# Diana.net
KiCad netlist of a schematic drawn in Altium Designer
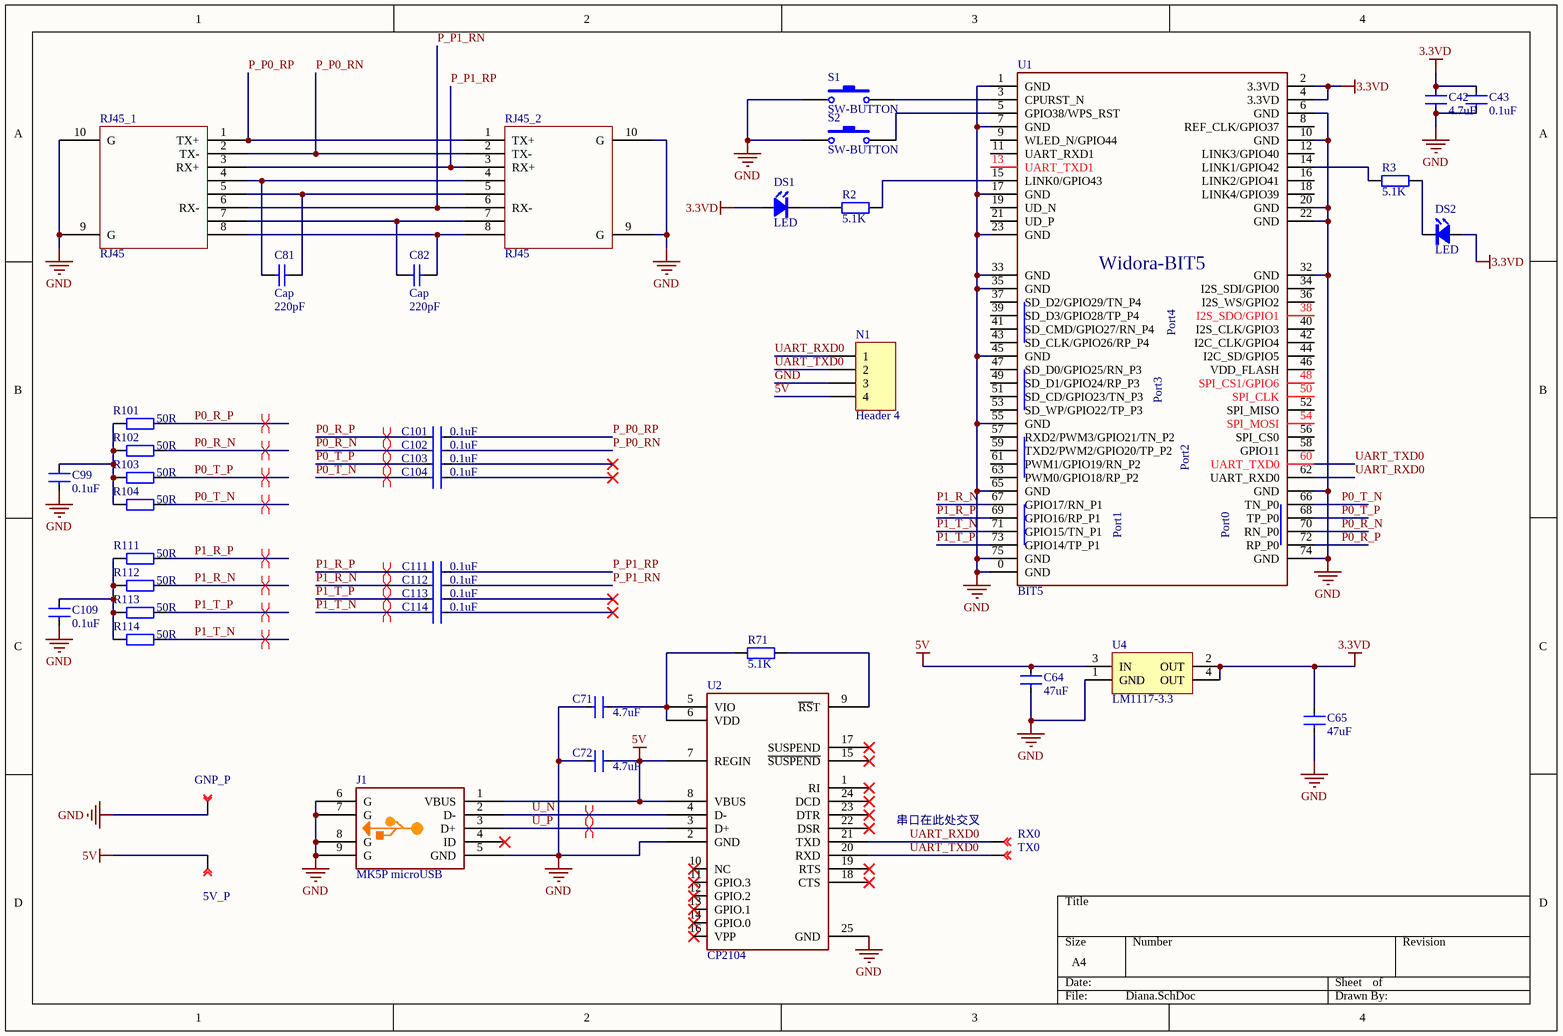
[diagram p0: Diana.SchDoc]

(export (version "E")
  (design (tool "Eeschema 10.0.6"))
  (components
    (comp (ref "5V_P")
      (value "TEST POINT")
      (footprint "TEST-POINT")
      (description "Description")
      (libsource (lib "KIT") (part "TP"))
    )
    (comp (ref "C42")
      (value "4.7uF")
      (footprint "C0402")
      (description "普通小电容")
      (libsource (lib "KIT") (part "CAP"))
    )
    (comp (ref "C43")
      (value "0.1uF")
      (footprint "C0402")
      (description "普通小电容")
      (libsource (lib "KIT") (part "CAP"))
    )
    (comp (ref "C64")
      (value "47uF")
      (footprint "0805C")
      (description "普通小电容")
      (libsource (lib "KIT") (part "CAP"))
    )
    (comp (ref "C65")
      (value "47uF")
      (footprint "0805C")
      (description "普通小电容")
      (libsource (lib "KIT") (part "CAP"))
    )
    (comp (ref "C71")
      (value "4.7uF")
      (footprint "C0402")
      (description "普通小电容")
      (libsource (lib "KIT") (part "CAP"))
    )
    (comp (ref "C72")
      (value "4.7uF")
      (footprint "C0402")
      (description "普通小电容")
      (libsource (lib "KIT") (part "CAP"))
    )
    (comp (ref "C81")
      (value "Cap")
      (footprint "C0402")
      (description "Capacitor")
      (fields (field (name "ALTIUM_VALUE") "220pF") (field (name "PUBLISHER") "Altium Limited"))
      (libsource (lib "Miscellaneous Devices") (part "Cap"))
    )
    (comp (ref "C82")
      (value "Cap")
      (footprint "C0402")
      (description "Capacitor")
      (fields (field (name "ALTIUM_VALUE") "220pF") (field (name "PUBLISHER") "Altium Limited"))
      (libsource (lib "Miscellaneous Devices") (part "Cap"))
    )
    (comp (ref "C99")
      (value "0.1uF")
      (footprint "C0402")
      (description "普通小电容")
      (libsource (lib "KIT") (part "CAP"))
    )
    (comp (ref "C101")
      (value "0.1uF")
      (footprint "C0402")
      (description "普通小电容")
      (libsource (lib "KIT") (part "CAP"))
    )
    (comp (ref "C102")
      (value "0.1uF")
      (footprint "C0402")
      (description "普通小电容")
      (libsource (lib "KIT") (part "CAP"))
    )
    (comp (ref "C103")
      (value "0.1uF")
      (footprint "C0402")
      (description "普通小电容")
      (libsource (lib "KIT") (part "CAP"))
    )
    (comp (ref "C104")
      (value "0.1uF")
      (footprint "C0402")
      (description "普通小电容")
      (libsource (lib "KIT") (part "CAP"))
    )
    (comp (ref "C109")
      (value "0.1uF")
      (footprint "C0402")
      (description "普通小电容")
      (libsource (lib "KIT") (part "CAP"))
    )
    (comp (ref "C111")
      (value "0.1uF")
      (footprint "C0402")
      (description "普通小电容")
      (libsource (lib "KIT") (part "CAP"))
    )
    (comp (ref "C112")
      (value "0.1uF")
      (footprint "C0402")
      (description "普通小电容")
      (libsource (lib "KIT") (part "CAP"))
    )
    (comp (ref "C113")
      (value "0.1uF")
      (footprint "C0402")
      (description "普通小电容")
      (libsource (lib "KIT") (part "CAP"))
    )
    (comp (ref "C114")
      (value "0.1uF")
      (footprint "C0402")
      (description "普通小电容")
      (libsource (lib "KIT") (part "CAP"))
    )
    (comp (ref "DS1")
      (value "LED")
      (footprint "LED0603")
      (description "RED")
      (libsource (lib "KIT") (part "LED"))
    )
    (comp (ref "DS2")
      (value "LED")
      (footprint "LED0603")
      (description "RED")
      (libsource (lib "") (part "LED_1"))
    )
    (comp (ref "GNP_P")
      (value "TEST POINT")
      (footprint "TEST-POINT")
      (description "Description")
      (libsource (lib "KIT") (part "TP"))
    )
    (comp (ref "J1")
      (value "MK5P microUSB")
      (footprint "MICROUSB")
      (description "4固定脚microUSB座")
      (libsource (lib "KIT") (part "MICRO_USB"))
    )
    (comp (ref "N1")
      (value "Header 4")
      (footprint "HDR-1X4")
      (description "Header, 4-Pin")
      (fields (field (name "PUBLISHER") "Altium Limited"))
      (libsource (lib "Miscellaneous Connectors") (part "Header 4"))
    )
    (comp (ref "R2")
      (value "5.1K")
      (footprint "R0402")
      (description "普通电阻")
      (libsource (lib "KIT") (part "RES"))
    )
    (comp (ref "R3")
      (value "5.1K")
      (footprint "R0402")
      (description "普通电阻")
      (libsource (lib "KIT") (part "RES"))
    )
    (comp (ref "R71")
      (value "5.1K")
      (footprint "R0402")
      (description "普通电阻")
      (libsource (lib "KIT") (part "RES"))
    )
    (comp (ref "R101")
      (value "50R")
      (footprint "R0402")
      (description "普通电阻")
      (libsource (lib "KIT") (part "RES"))
    )
    (comp (ref "R102")
      (value "50R")
      (footprint "R0402")
      (description "普通电阻")
      (libsource (lib "KIT") (part "RES"))
    )
    (comp (ref "R103")
      (value "50R")
      (footprint "R0402")
      (description "普通电阻")
      (libsource (lib "KIT") (part "RES"))
    )
    (comp (ref "R104")
      (value "50R")
      (footprint "R0402")
      (description "普通电阻")
      (libsource (lib "KIT") (part "RES"))
    )
    (comp (ref "R111")
      (value "50R")
      (footprint "R0402")
      (description "普通电阻")
      (libsource (lib "KIT") (part "RES"))
    )
    (comp (ref "R112")
      (value "50R")
      (footprint "R0402")
      (description "普通电阻")
      (libsource (lib "KIT") (part "RES"))
    )
    (comp (ref "R113")
      (value "50R")
      (footprint "R0402")
      (description "普通电阻")
      (libsource (lib "KIT") (part "RES"))
    )
    (comp (ref "R114")
      (value "50R")
      (footprint "R0402")
      (description "普通电阻")
      (libsource (lib "KIT") (part "RES"))
    )
    (comp (ref "RJ45_1")
      (value "RJ45")
      (footprint "RJ45")
      (description "RJ45不带网络变压器")
      (libsource (lib "KIT") (part "RJ45"))
    )
    (comp (ref "RJ45_2")
      (value "RJ45")
      (footprint "RJ45")
      (description "RJ45不带网络变压器")
      (libsource (lib "") (part "RJ45_1"))
    )
    (comp (ref "RX0")
      (value "TEST POINT")
      (footprint "TEST-POINT")
      (description "Description")
      (libsource (lib "KIT") (part "TP"))
    )
    (comp (ref "S1") (value "SW-BUTTON") (footprint "MINIBUTTON") (libsource (lib "KIT") (part "SW-BUTTON")))
    (comp (ref "S2") (value "SW-BUTTON") (footprint "MINIBUTTON") (libsource (lib "KIT") (part "SW-BUTTON")))
    (comp (ref "TX0")
      (value "TEST POINT")
      (footprint "TEST-POINT")
      (description "Description")
      (libsource (lib "KIT") (part "TP"))
    )
    (comp (ref "U1")
      (value "BIT5")
      (footprint "NGFF_M_2-EKEY")
      (description "NGFF M.2 E KEY")
      (libsource (lib "BIT345") (part "BIT5"))
    )
    (comp (ref "U2") (value "CP2104") (footprint "QFN24") (libsource (lib "KIT") (part "CP2104")))
    (comp (ref "U4")
      (value "LM1117-3.3")
      (footprint "SOT223-4N")
      (description "800mA and 1A Low Dropout Positive Regulator 2.85V, 3.3V, 5V, and Adjustable")
      (fields (field (name "PUBLISHER") "Altium Limited"))
      (libsource (lib "KIT") (part "LM1117-3.3"))
    )
  )
  (nets
    (net (code "1") (name "/P0_R_N") (class "Default")
      (node (ref "C102") (pin "1") (pinfunction "1_1") (pintype "passive"))
      (node (ref "R102") (pin "2") (pinfunction "2_2") (pintype "passive"))
      (node (ref "U1") (pin "70") (pinfunction "RN_P0_70") (pintype "passive"))
    )
    (net (code "2") (name "/P0_R_P") (class "Default")
      (node (ref "C101") (pin "1") (pinfunction "1_1") (pintype "passive"))
      (node (ref "R101") (pin "2") (pinfunction "2_2") (pintype "passive"))
      (node (ref "U1") (pin "72") (pinfunction "RP_P0_72") (pintype "passive"))
    )
    (net (code "3") (name "/P0_T_N") (class "Default")
      (node (ref "C104") (pin "1") (pinfunction "1_1") (pintype "passive"))
      (node (ref "R104") (pin "2") (pinfunction "2_2") (pintype "passive"))
      (node (ref "U1") (pin "66") (pinfunction "TN_P0_66") (pintype "passive"))
    )
    (net (code "4") (name "/P0_T_P") (class "Default")
      (node (ref "C103") (pin "1") (pinfunction "1_1") (pintype "passive"))
      (node (ref "R103") (pin "2") (pinfunction "2_2") (pintype "passive"))
      (node (ref "U1") (pin "68") (pinfunction "TP_P0_68") (pintype "passive"))
    )
    (net (code "5") (name "/P1_R_N") (class "Default")
      (node (ref "C112") (pin "1") (pinfunction "1_1") (pintype "passive"))
      (node (ref "R112") (pin "2") (pinfunction "2_2") (pintype "passive"))
      (node (ref "U1") (pin "67") (pinfunction "GPIO17/RN_P1_67") (pintype "passive"))
    )
    (net (code "6") (name "/P1_R_P") (class "Default")
      (node (ref "C111") (pin "1") (pinfunction "1_1") (pintype "passive"))
      (node (ref "R111") (pin "2") (pinfunction "2_2") (pintype "passive"))
      (node (ref "U1") (pin "69") (pinfunction "GPIO16/RP_P1_69") (pintype "passive"))
    )
    (net (code "7") (name "/P1_T_N") (class "Default")
      (node (ref "C114") (pin "1") (pinfunction "1_1") (pintype "passive"))
      (node (ref "R114") (pin "2") (pinfunction "2_2") (pintype "passive"))
      (node (ref "U1") (pin "71") (pinfunction "GPIO15/TN_P1_71") (pintype "passive"))
    )
    (net (code "8") (name "/P1_T_P") (class "Default")
      (node (ref "C113") (pin "1") (pinfunction "1_1") (pintype "passive"))
      (node (ref "R113") (pin "2") (pinfunction "2_2") (pintype "passive"))
      (node (ref "U1") (pin "73") (pinfunction "GPIO14/TP_P1_73") (pintype "passive"))
    )
    (net (code "9") (name "/P_P0_RN") (class "Default")
      (node (ref "C102") (pin "2") (pinfunction "2_2") (pintype "passive"))
      (node (ref "RJ45_1") (pin "2") (pinfunction "TX-_2") (pintype "power_in"))
      (node (ref "RJ45_2") (pin "2") (pinfunction "TX-_2") (pintype "power_in"))
    )
    (net (code "10") (name "/P_P0_RP") (class "Default")
      (node (ref "C101") (pin "2") (pinfunction "2_2") (pintype "passive"))
      (node (ref "RJ45_1") (pin "1") (pinfunction "TX+_1") (pintype "power_in"))
      (node (ref "RJ45_2") (pin "1") (pinfunction "TX+_1") (pintype "power_in"))
    )
    (net (code "11") (name "/P_P1_RN") (class "Default")
      (node (ref "C112") (pin "2") (pinfunction "2_2") (pintype "passive"))
      (node (ref "RJ45_1") (pin "6") (pinfunction "RX-_6") (pintype "power_in"))
      (node (ref "RJ45_2") (pin "6") (pinfunction "RX-_6") (pintype "power_in"))
    )
    (net (code "12") (name "/P_P1_RP") (class "Default")
      (node (ref "C111") (pin "2") (pinfunction "2_2") (pintype "passive"))
      (node (ref "RJ45_1") (pin "3") (pinfunction "RX+_3") (pintype "power_in"))
      (node (ref "RJ45_2") (pin "3") (pinfunction "RX+_3") (pintype "power_in"))
    )
    (net (code "13") (name "/UART_RXD0") (class "Default")
      (node (ref "N1") (pin "1") (pinfunction "1_1") (pintype "passive"))
      (node (ref "RX0") (pin "1") (pinfunction "1_1") (pintype "passive"))
      (node (ref "U1") (pin "62") (pinfunction "UART_RXD0_62") (pintype "passive"))
      (node (ref "U2") (pin "21") (pinfunction "TXD_21") (pintype "passive"))
    )
    (net (code "14") (name "/UART_TXD0") (class "Default")
      (node (ref "N1") (pin "2") (pinfunction "2_2") (pintype "passive"))
      (node (ref "TX0") (pin "1") (pinfunction "1_1") (pintype "passive"))
      (node (ref "U1") (pin "60") (pinfunction "UART_TXD0_60") (pintype "passive"))
      (node (ref "U2") (pin "20") (pinfunction "RXD_20") (pintype "passive"))
    )
    (net (code "15") (name "/U_N") (class "Default")
      (node (ref "J1") (pin "2") (pinfunction "D-_2") (pintype "passive"))
      (node (ref "U2") (pin "4") (pinfunction "D-_4") (pintype "passive"))
    )
    (net (code "16") (name "/U_P") (class "Default")
      (node (ref "J1") (pin "3") (pinfunction "D+_3") (pintype "passive"))
      (node (ref "U2") (pin "3") (pinfunction "D+_3") (pintype "passive"))
    )
    (net (code "17") (name "3.3VD") (class "Default")
      (node (ref "C42") (pin "1") (pinfunction "1_1") (pintype "passive"))
      (node (ref "C43") (pin "1") (pinfunction "1_1") (pintype "passive"))
      (node (ref "C65") (pin "2") (pinfunction "2_2") (pintype "passive"))
      (node (ref "DS1") (pin "A") (pinfunction "1_A") (pintype "passive"))
      (node (ref "DS2") (pin "A") (pinfunction "1_A") (pintype "passive"))
      (node (ref "U1") (pin "2") (pinfunction "3.3VD_2") (pintype "passive"))
      (node (ref "U1") (pin "4") (pinfunction "3.3VD_4") (pintype "passive"))
      (node (ref "U4") (pin "2") (pinfunction "OUT_2") (pintype "power_in"))
      (node (ref "U4") (pin "4") (pinfunction "OUT_4") (pintype "power_in"))
    )
    (net (code "18") (name "5V") (class "Default")
      (node (ref "5V_P") (pin "1") (pinfunction "1_1") (pintype "passive"))
      (node (ref "C64") (pin "1") (pinfunction "1_1") (pintype "passive"))
      (node (ref "C72") (pin "2") (pinfunction "2_2") (pintype "passive"))
      (node (ref "J1") (pin "1") (pinfunction "VBUS_1") (pintype "power_in"))
      (node (ref "N1") (pin "4") (pinfunction "4_4") (pintype "passive"))
      (node (ref "U2") (pin "7") (pinfunction "REGIN_7") (pintype "passive"))
      (node (ref "U2") (pin "8") (pinfunction "VBUS_8") (pintype "power_in"))
      (node (ref "U4") (pin "3") (pinfunction "IN_3") (pintype "power_in"))
    )
    (net (code "19") (name "GND") (class "Default")
      (node (ref "C109") (pin "2") (pinfunction "2_2") (pintype "passive"))
      (node (ref "C42") (pin "2") (pinfunction "2_2") (pintype "passive"))
      (node (ref "C43") (pin "2") (pinfunction "2_2") (pintype "passive"))
      (node (ref "C64") (pin "2") (pinfunction "2_2") (pintype "passive"))
      (node (ref "C65") (pin "1") (pinfunction "1_1") (pintype "passive"))
      (node (ref "C71") (pin "2") (pinfunction "2_2") (pintype "passive"))
      (node (ref "C72") (pin "1") (pinfunction "1_1") (pintype "passive"))
      (node (ref "C99") (pin "2") (pinfunction "2_2") (pintype "passive"))
      (node (ref "GNP_P") (pin "1") (pinfunction "1_1") (pintype "passive"))
      (node (ref "J1") (pin "5") (pinfunction "GND_5") (pintype "power_in"))
      (node (ref "J1") (pin "6") (pinfunction "G_6") (pintype "passive"))
      (node (ref "J1") (pin "7") (pinfunction "G_7") (pintype "passive"))
      (node (ref "J1") (pin "8") (pinfunction "G_8") (pintype "passive"))
      (node (ref "J1") (pin "9") (pinfunction "G_9") (pintype "passive"))
      (node (ref "N1") (pin "3") (pinfunction "3_3") (pintype "passive"))
      (node (ref "RJ45_1") (pin "10") (pinfunction "G_10") (pintype "power_in"))
      (node (ref "RJ45_1") (pin "9") (pinfunction "G_9") (pintype "power_in"))
      (node (ref "RJ45_2") (pin "10") (pinfunction "G_10") (pintype "power_in"))
      (node (ref "RJ45_2") (pin "9") (pinfunction "G_9") (pintype "power_in"))
      (node (ref "S1") (pin "1") (pinfunction "1_1") (pintype "passive"))
      (node (ref "S2") (pin "1") (pinfunction "1_1") (pintype "passive"))
      (node (ref "U1") (pin "0") (pinfunction "GND_0") (pintype "passive"))
      (node (ref "U1") (pin "1") (pinfunction "GND_1") (pintype "passive"))
      (node (ref "U1") (pin "10") (pinfunction "GND_10") (pintype "passive"))
      (node (ref "U1") (pin "17") (pinfunction "GND_17") (pintype "passive"))
      (node (ref "U1") (pin "20") (pinfunction "GND_20") (pintype "passive"))
      (node (ref "U1") (pin "22") (pinfunction "GND_22") (pintype "passive"))
      (node (ref "U1") (pin "23") (pinfunction "GND_23") (pintype "passive"))
      (node (ref "U1") (pin "32") (pinfunction "GND_32") (pintype "passive"))
      (node (ref "U1") (pin "33") (pinfunction "GND_33") (pintype "passive"))
      (node (ref "U1") (pin "35") (pinfunction "GND_35") (pintype "passive"))
      (node (ref "U1") (pin "45") (pinfunction "GND_45") (pintype "passive"))
      (node (ref "U1") (pin "55") (pinfunction "GND_55") (pintype "passive"))
      (node (ref "U1") (pin "6") (pinfunction "GND_6") (pintype "passive"))
      (node (ref "U1") (pin "64") (pinfunction "GND_64") (pintype "passive"))
      (node (ref "U1") (pin "65") (pinfunction "GND_65") (pintype "passive"))
      (node (ref "U1") (pin "7") (pinfunction "GND_7") (pintype "passive"))
      (node (ref "U1") (pin "74") (pinfunction "GND_74") (pintype "passive"))
      (node (ref "U1") (pin "75") (pinfunction "GND_75") (pintype "passive"))
      (node (ref "U2") (pin "2") (pinfunction "GND_2") (pintype "power_in"))
      (node (ref "U2") (pin "25") (pinfunction "GND_25") (pintype "power_in"))
      (node (ref "U4") (pin "1") (pinfunction "GND_1") (pintype "power_in"))
    )
    (net (code "20") (name "Net-(C81-Pad1)") (class "Default")
      (node (ref "C81") (pin "1") (pinfunction "1_1") (pintype "passive"))
      (node (ref "RJ45_1") (pin "4") (pintype "power_in"))
      (node (ref "RJ45_2") (pin "4") (pintype "power_in"))
    )
    (net (code "21") (name "Net-(C81-Pad2)") (class "Default")
      (node (ref "C81") (pin "2") (pinfunction "2_2") (pintype "passive"))
      (node (ref "RJ45_1") (pin "5") (pintype "power_in"))
      (node (ref "RJ45_2") (pin "5") (pintype "power_in"))
    )
    (net (code "22") (name "Net-(C82-Pad1)") (class "Default")
      (node (ref "C82") (pin "1") (pinfunction "1_1") (pintype "passive"))
      (node (ref "RJ45_1") (pin "7") (pintype "power_in"))
      (node (ref "RJ45_2") (pin "7") (pintype "power_in"))
    )
    (net (code "23") (name "Net-(C82-Pad2)") (class "Default")
      (node (ref "C82") (pin "2") (pinfunction "2_2") (pintype "passive"))
      (node (ref "RJ45_1") (pin "8") (pintype "power_in"))
      (node (ref "RJ45_2") (pin "8") (pintype "power_in"))
    )
    (net (code "24") (name "Net-(C99-Pad1)") (class "Default")
      (node (ref "C99") (pin "1") (pinfunction "1_1") (pintype "passive"))
      (node (ref "R101") (pin "1") (pinfunction "1_1") (pintype "passive"))
      (node (ref "R102") (pin "1") (pinfunction "1_1") (pintype "passive"))
      (node (ref "R103") (pin "1") (pinfunction "1_1") (pintype "passive"))
      (node (ref "R104") (pin "1") (pinfunction "1_1") (pintype "passive"))
    )
    (net (code "25") (name "Net-(C109-Pad1)") (class "Default")
      (node (ref "C109") (pin "1") (pinfunction "1_1") (pintype "passive"))
      (node (ref "R111") (pin "1") (pinfunction "1_1") (pintype "passive"))
      (node (ref "R112") (pin "1") (pinfunction "1_1") (pintype "passive"))
      (node (ref "R113") (pin "1") (pinfunction "1_1") (pintype "passive"))
      (node (ref "R114") (pin "1") (pinfunction "1_1") (pintype "passive"))
    )
    (net (code "26") (name "Net-(DS1-2)") (class "Default")
      (node (ref "DS1") (pin "K") (pinfunction "2_K") (pintype "passive"))
      (node (ref "R2") (pin "1") (pinfunction "1_1") (pintype "passive"))
    )
    (net (code "27") (name "Net-(DS2-2)") (class "Default")
      (node (ref "DS2") (pin "K") (pinfunction "2_K") (pintype "passive"))
      (node (ref "R3") (pin "2") (pinfunction "2_2") (pintype "passive"))
    )
    (net (code "28") (name "Net-(U1-CPURST_N)") (class "Default")
      (node (ref "S1") (pin "2") (pinfunction "2_2") (pintype "passive"))
      (node (ref "U1") (pin "3") (pinfunction "CPURST_N_3") (pintype "passive"))
    )
    (net (code "29") (name "Net-(U1-GPIO38{slash}WPS_RST)") (class "Default")
      (node (ref "S2") (pin "2") (pinfunction "2_2") (pintype "passive"))
      (node (ref "U1") (pin "5") (pinfunction "GPIO38/WPS_RST_5") (pintype "passive"))
    )
    (net (code "30") (name "Net-(U1-LINK0{slash}GPIO43)") (class "Default")
      (node (ref "R2") (pin "2") (pinfunction "2_2") (pintype "passive"))
      (node (ref "U1") (pin "15") (pinfunction "LINK0/GPIO43_15") (pintype "passive"))
    )
    (net (code "31") (name "Net-(U1-LINK1{slash}GPIO42)") (class "Default")
      (node (ref "R3") (pin "1") (pinfunction "1_1") (pintype "passive"))
      (node (ref "U1") (pin "14") (pinfunction "LINK1/GPIO42_14") (pintype "passive"))
    )
    (net (code "32") (name "Net-(U2-VDD)") (class "Default")
      (node (ref "C71") (pin "1") (pinfunction "1_1") (pintype "passive"))
      (node (ref "R71") (pin "1") (pinfunction "1_1") (pintype "passive"))
      (node (ref "U2") (pin "5") (pinfunction "VIO_5") (pintype "passive"))
      (node (ref "U2") (pin "6") (pinfunction "VDD_6") (pintype "passive"))
    )
    (net (code "33") (name "Net-(U2-~{RS}T)") (class "Default")
      (node (ref "R71") (pin "2") (pinfunction "2_2") (pintype "passive"))
      (node (ref "U2") (pin "9") (pinfunction "~{RS}T_9") (pintype "passive"))
    )
    (net (code "34") (name "unconnected-(C103-Pad2)") (class "Default")
      (node (ref "C103") (pin "2") (pinfunction "2_2") (pintype "passive+no_connect"))
    )
    (net (code "35") (name "unconnected-(C104-Pad2)") (class "Default")
      (node (ref "C104") (pin "2") (pinfunction "2_2") (pintype "passive+no_connect"))
    )
    (net (code "36") (name "unconnected-(C113-Pad2)") (class "Default")
      (node (ref "C113") (pin "2") (pinfunction "2_2") (pintype "passive+no_connect"))
    )
    (net (code "37") (name "unconnected-(C114-Pad2)") (class "Default")
      (node (ref "C114") (pin "2") (pinfunction "2_2") (pintype "passive+no_connect"))
    )
    (net (code "38") (name "unconnected-(J1-ID-Pad4)") (class "Default")
      (node (ref "J1") (pin "4") (pinfunction "ID_4") (pintype "passive+no_connect"))
    )
    (net (code "39") (name "unconnected-(U1-GPIO11-Pad58)") (class "Default")
      (node (ref "U1") (pin "58") (pinfunction "GPIO11_58") (pintype "passive"))
    )
    (net (code "40") (name "unconnected-(U1-I2C_CLK{slash}GPIO4-Pad42)") (class "Default")
      (node (ref "U1") (pin "42") (pinfunction "I2C_CLK/GPIO4_42") (pintype "passive"))
    )
    (net (code "41") (name "unconnected-(U1-I2C_SD{slash}GPIO5-Pad44)") (class "Default")
      (node (ref "U1") (pin "44") (pinfunction "I2C_SD/GPIO5_44") (pintype "passive"))
    )
    (net (code "42") (name "unconnected-(U1-I2S_CLK{slash}GPIO3-Pad40)") (class "Default")
      (node (ref "U1") (pin "40") (pinfunction "I2S_CLK/GPIO3_40") (pintype "passive"))
    )
    (net (code "43") (name "unconnected-(U1-I2S_SDI{slash}GPIO0-Pad34)") (class "Default")
      (node (ref "U1") (pin "34") (pinfunction "I2S_SDI/GPIO0_34") (pintype "passive"))
    )
    (net (code "44") (name "unconnected-(U1-I2S_SDO{slash}GPIO1-Pad38)") (class "Default")
      (node (ref "U1") (pin "38") (pinfunction "I2S_SDO/GPIO1_38") (pintype "passive"))
    )
    (net (code "45") (name "unconnected-(U1-I2S_WS{slash}GPIO2-Pad36)") (class "Default")
      (node (ref "U1") (pin "36") (pinfunction "I2S_WS/GPIO2_36") (pintype "passive"))
    )
    (net (code "46") (name "unconnected-(U1-LINK2{slash}GPIO41-Pad16)") (class "Default")
      (node (ref "U1") (pin "16") (pinfunction "LINK2/GPIO41_16") (pintype "passive"))
    )
    (net (code "47") (name "unconnected-(U1-LINK3{slash}GPIO40-Pad12)") (class "Default")
      (node (ref "U1") (pin "12") (pinfunction "LINK3/GPIO40_12") (pintype "passive"))
    )
    (net (code "48") (name "unconnected-(U1-LINK4{slash}GPIO39-Pad18)") (class "Default")
      (node (ref "U1") (pin "18") (pinfunction "LINK4/GPIO39_18") (pintype "passive"))
    )
    (net (code "49") (name "unconnected-(U1-PWM0{slash}GPIO18{slash}RP_P2-Pad63)") (class "Default")
      (node (ref "U1") (pin "63") (pinfunction "PWM0/GPIO18/RP_P2_63") (pintype "passive"))
    )
    (net (code "50") (name "unconnected-(U1-PWM1{slash}GPIO19{slash}RN_P2-Pad61)") (class "Default")
      (node (ref "U1") (pin "61") (pinfunction "PWM1/GPIO19/RN_P2_61") (pintype "passive"))
    )
    (net (code "51") (name "unconnected-(U1-REF_CLK{slash}GPIO37-Pad8)") (class "Default")
      (node (ref "U1") (pin "8") (pinfunction "REF_CLK/GPIO37_8") (pintype "passive"))
    )
    (net (code "52") (name "unconnected-(U1-RXD2{slash}PWM3{slash}GPIO21{slash}TN_P2-Pad57)") (class "Default")
      (node (ref "U1") (pin "57") (pinfunction "RXD2/PWM3/GPIO21/TN_P2_57") (pintype "passive"))
    )
    (net (code "53") (name "unconnected-(U1-SD_CD{slash}GPIO23{slash}TN_P3-Pad51)") (class "Default")
      (node (ref "U1") (pin "51") (pinfunction "SD_CD/GPIO23/TN_P3_51") (pintype "passive"))
    )
    (net (code "54") (name "unconnected-(U1-SD_CLK{slash}GPIO26{slash}RP_P4-Pad43)") (class "Default")
      (node (ref "U1") (pin "43") (pinfunction "SD_CLK/GPIO26/RP_P4_43") (pintype "passive"))
    )
    (net (code "55") (name "unconnected-(U1-SD_CMD{slash}GPIO27{slash}RN_P4-Pad41)") (class "Default")
      (node (ref "U1") (pin "41") (pinfunction "SD_CMD/GPIO27/RN_P4_41") (pintype "passive"))
    )
    (net (code "56") (name "unconnected-(U1-SD_D0{slash}GPIO25{slash}RN_P3-Pad47)") (class "Default")
      (node (ref "U1") (pin "47") (pinfunction "SD_D0/GPIO25/RN_P3_47") (pintype "passive"))
    )
    (net (code "57") (name "unconnected-(U1-SD_D1{slash}GPIO24{slash}RP_P3-Pad49)") (class "Default")
      (node (ref "U1") (pin "49") (pinfunction "SD_D1/GPIO24/RP_P3_49") (pintype "passive"))
    )
    (net (code "58") (name "unconnected-(U1-SD_D2{slash}GPIO29{slash}TN_P4-Pad37)") (class "Default")
      (node (ref "U1") (pin "37") (pinfunction "SD_D2/GPIO29/TN_P4_37") (pintype "passive"))
    )
    (net (code "59") (name "unconnected-(U1-SD_D3{slash}GPIO28{slash}TP_P4-Pad39)") (class "Default")
      (node (ref "U1") (pin "39") (pinfunction "SD_D3/GPIO28/TP_P4_39") (pintype "passive"))
    )
    (net (code "60") (name "unconnected-(U1-SD_WP{slash}GPIO22{slash}TP_P3-Pad53)") (class "Default")
      (node (ref "U1") (pin "53") (pinfunction "SD_WP/GPIO22/TP_P3_53") (pintype "passive"))
    )
    (net (code "61") (name "unconnected-(U1-SPI_CLK-Pad50)") (class "Default")
      (node (ref "U1") (pin "50") (pinfunction "SPI_CLK_50") (pintype "passive"))
    )
    (net (code "62") (name "unconnected-(U1-SPI_CS0-Pad56)") (class "Default")
      (node (ref "U1") (pin "56") (pinfunction "SPI_CS0_56") (pintype "passive"))
    )
    (net (code "63") (name "unconnected-(U1-SPI_CS1{slash}GPIO6-Pad48)") (class "Default")
      (node (ref "U1") (pin "48") (pinfunction "SPI_CS1/GPIO6_48") (pintype "passive"))
    )
    (net (code "64") (name "unconnected-(U1-SPI_MISO-Pad52)") (class "Default")
      (node (ref "U1") (pin "52") (pinfunction "SPI_MISO_52") (pintype "passive"))
    )
    (net (code "65") (name "unconnected-(U1-SPI_MOSI-Pad54)") (class "Default")
      (node (ref "U1") (pin "54") (pinfunction "SPI_MOSI_54") (pintype "passive"))
    )
    (net (code "66") (name "unconnected-(U1-TXD2{slash}PWM2{slash}GPIO20{slash}TP_P2-Pad59)") (class "Default")
      (node (ref "U1") (pin "59") (pinfunction "TXD2/PWM2/GPIO20/TP_P2_59") (pintype "passive"))
    )
    (net (code "67") (name "unconnected-(U1-UART_RXD1-Pad11)") (class "Default")
      (node (ref "U1") (pin "11") (pinfunction "UART_RXD1_11") (pintype "passive"))
    )
    (net (code "68") (name "unconnected-(U1-UART_TXD1-Pad13)") (class "Default")
      (node (ref "U1") (pin "13") (pinfunction "UART_TXD1_13") (pintype "passive"))
    )
    (net (code "69") (name "unconnected-(U1-UD_N-Pad19)") (class "Default")
      (node (ref "U1") (pin "19") (pinfunction "UD_N_19") (pintype "passive"))
    )
    (net (code "70") (name "unconnected-(U1-UD_P-Pad21)") (class "Default")
      (node (ref "U1") (pin "21") (pinfunction "UD_P_21") (pintype "passive"))
    )
    (net (code "71") (name "unconnected-(U1-VDD_FLASH-Pad46)") (class "Default")
      (node (ref "U1") (pin "46") (pinfunction "VDD_FLASH_46") (pintype "passive"))
    )
    (net (code "72") (name "unconnected-(U1-WLED_N{slash}GPIO44-Pad9)") (class "Default")
      (node (ref "U1") (pin "9") (pinfunction "WLED_N/GPIO44_9") (pintype "passive"))
    )
    (net (code "73") (name "unconnected-(U2-CTS-Pad18)") (class "Default")
      (node (ref "U2") (pin "18") (pinfunction "CTS_18") (pintype "passive+no_connect"))
    )
    (net (code "74") (name "unconnected-(U2-DCD-Pad24)") (class "Default")
      (node (ref "U2") (pin "24") (pinfunction "DCD_24") (pintype "passive+no_connect"))
    )
    (net (code "75") (name "unconnected-(U2-DSR-Pad22)") (class "Default")
      (node (ref "U2") (pin "22") (pinfunction "DSR_22") (pintype "passive+no_connect"))
    )
    (net (code "76") (name "unconnected-(U2-DTR-Pad23)") (class "Default")
      (node (ref "U2") (pin "23") (pinfunction "DTR_23") (pintype "passive+no_connect"))
    )
    (net (code "77") (name "unconnected-(U2-GPIO.0-Pad14)") (class "Default")
      (node (ref "U2") (pin "14") (pinfunction "GPIO.0_14") (pintype "passive+no_connect"))
    )
    (net (code "78") (name "unconnected-(U2-GPIO.1-Pad13)") (class "Default")
      (node (ref "U2") (pin "13") (pinfunction "GPIO.1_13") (pintype "passive+no_connect"))
    )
    (net (code "79") (name "unconnected-(U2-GPIO.2-Pad12)") (class "Default")
      (node (ref "U2") (pin "12") (pinfunction "GPIO.2_12") (pintype "passive+no_connect"))
    )
    (net (code "80") (name "unconnected-(U2-GPIO.3-Pad11)") (class "Default")
      (node (ref "U2") (pin "11") (pinfunction "GPIO.3_11") (pintype "passive+no_connect"))
    )
    (net (code "81") (name "unconnected-(U2-NC-Pad10)") (class "Default")
      (node (ref "U2") (pin "10") (pinfunction "NC_10") (pintype "passive+no_connect"))
    )
    (net (code "82") (name "unconnected-(U2-RI-Pad1)") (class "Default")
      (node (ref "U2") (pin "1") (pinfunction "RI_1") (pintype "passive+no_connect"))
    )
    (net (code "83") (name "unconnected-(U2-RTS-Pad19)") (class "Default")
      (node (ref "U2") (pin "19") (pinfunction "RTS_19") (pintype "passive+no_connect"))
    )
    (net (code "84") (name "unconnected-(U2-SUSPEND-Pad17)") (class "Default")
      (node (ref "U2") (pin "17") (pinfunction "SUSPEND_17") (pintype "passive+no_connect"))
    )
    (net (code "85") (name "unconnected-(U2-VPP-Pad16)") (class "Default")
      (node (ref "U2") (pin "16") (pinfunction "VPP_16") (pintype "passive+no_connect"))
    )
    (net (code "86") (name "unconnected-(U2-~{SUSPEND}-Pad15)") (class "Default")
      (node (ref "U2") (pin "15") (pinfunction "~{SUSPEND}_15") (pintype "passive+no_connect"))
    )
  )
)
